# MAX96724_EVB_revB.net
KiCad netlist of a schematic drawn in Altium Designer
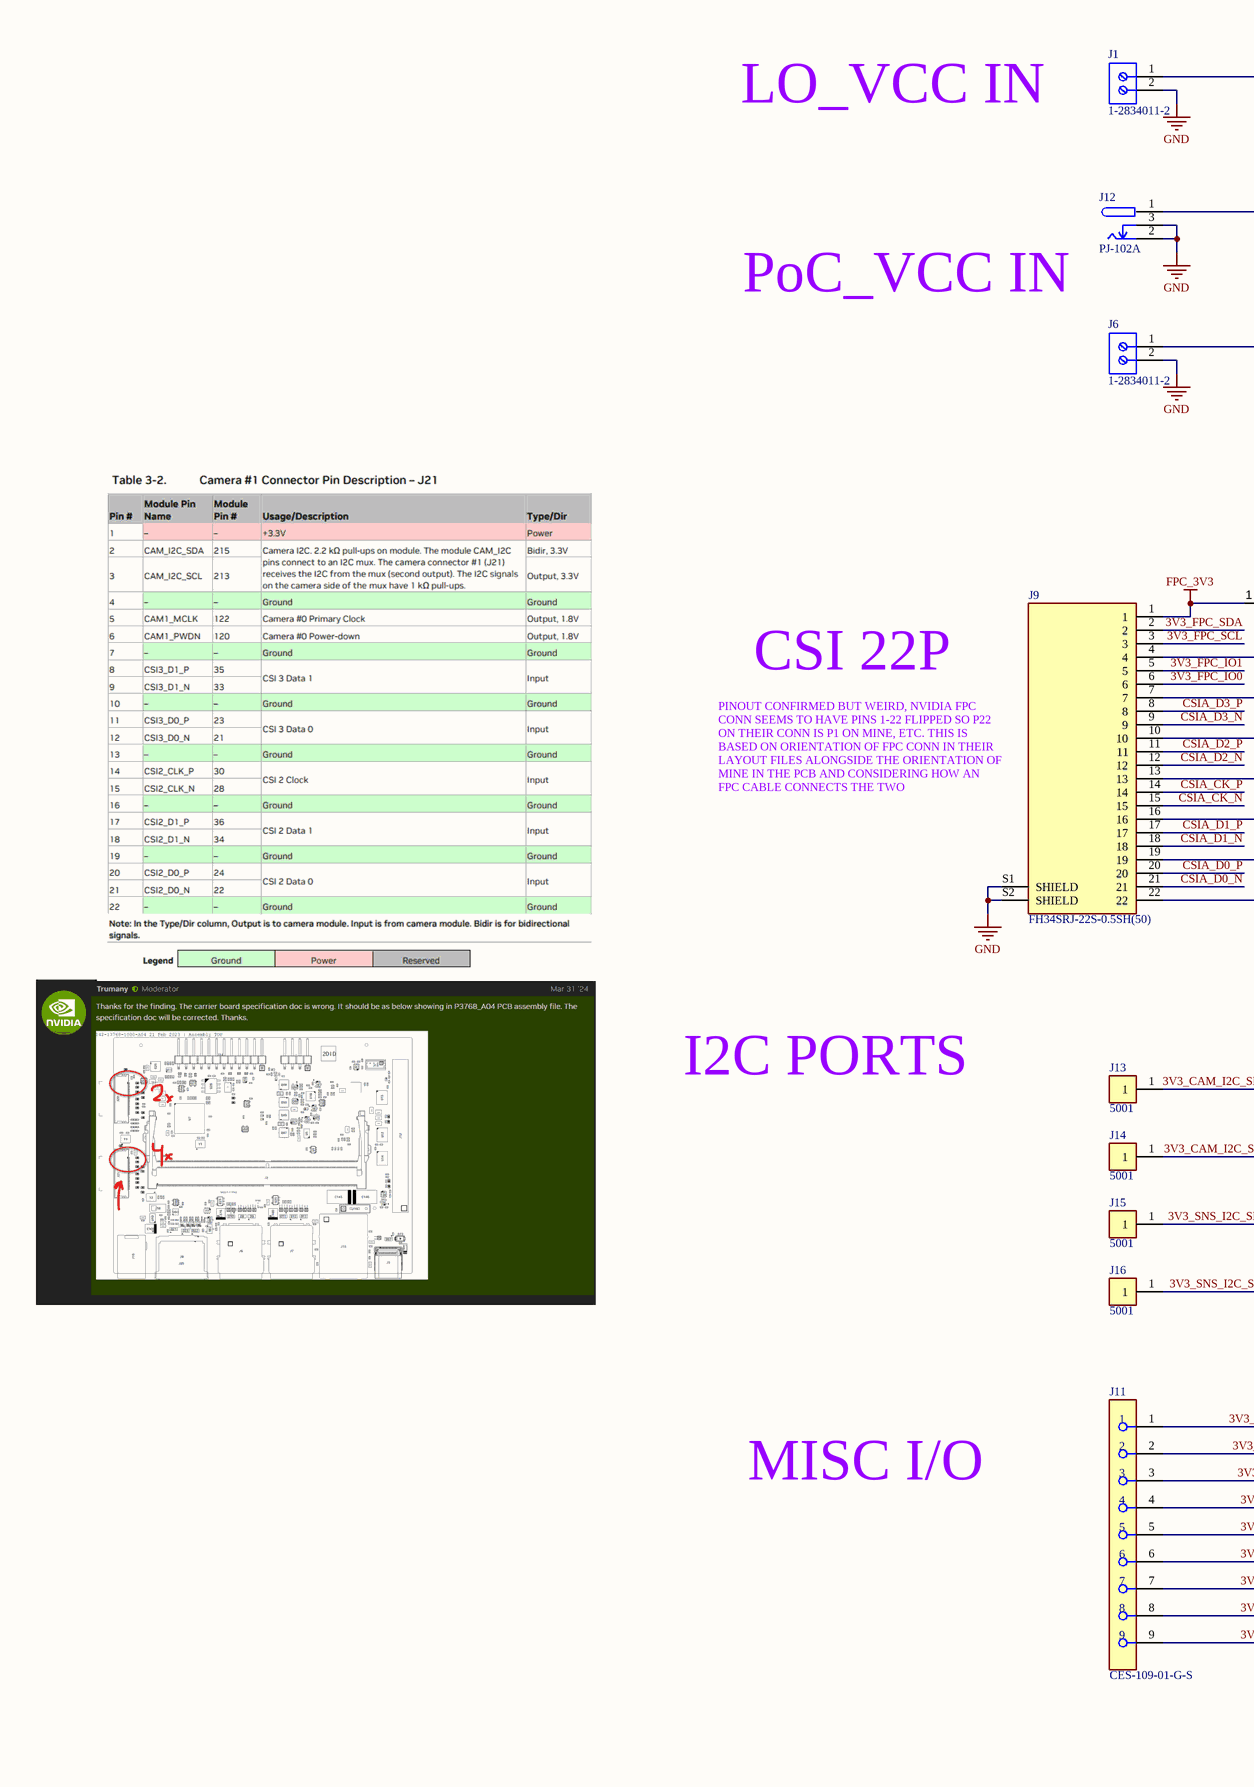
[diagram p0: MAX96724_EVB_revB.SchDoc, left]
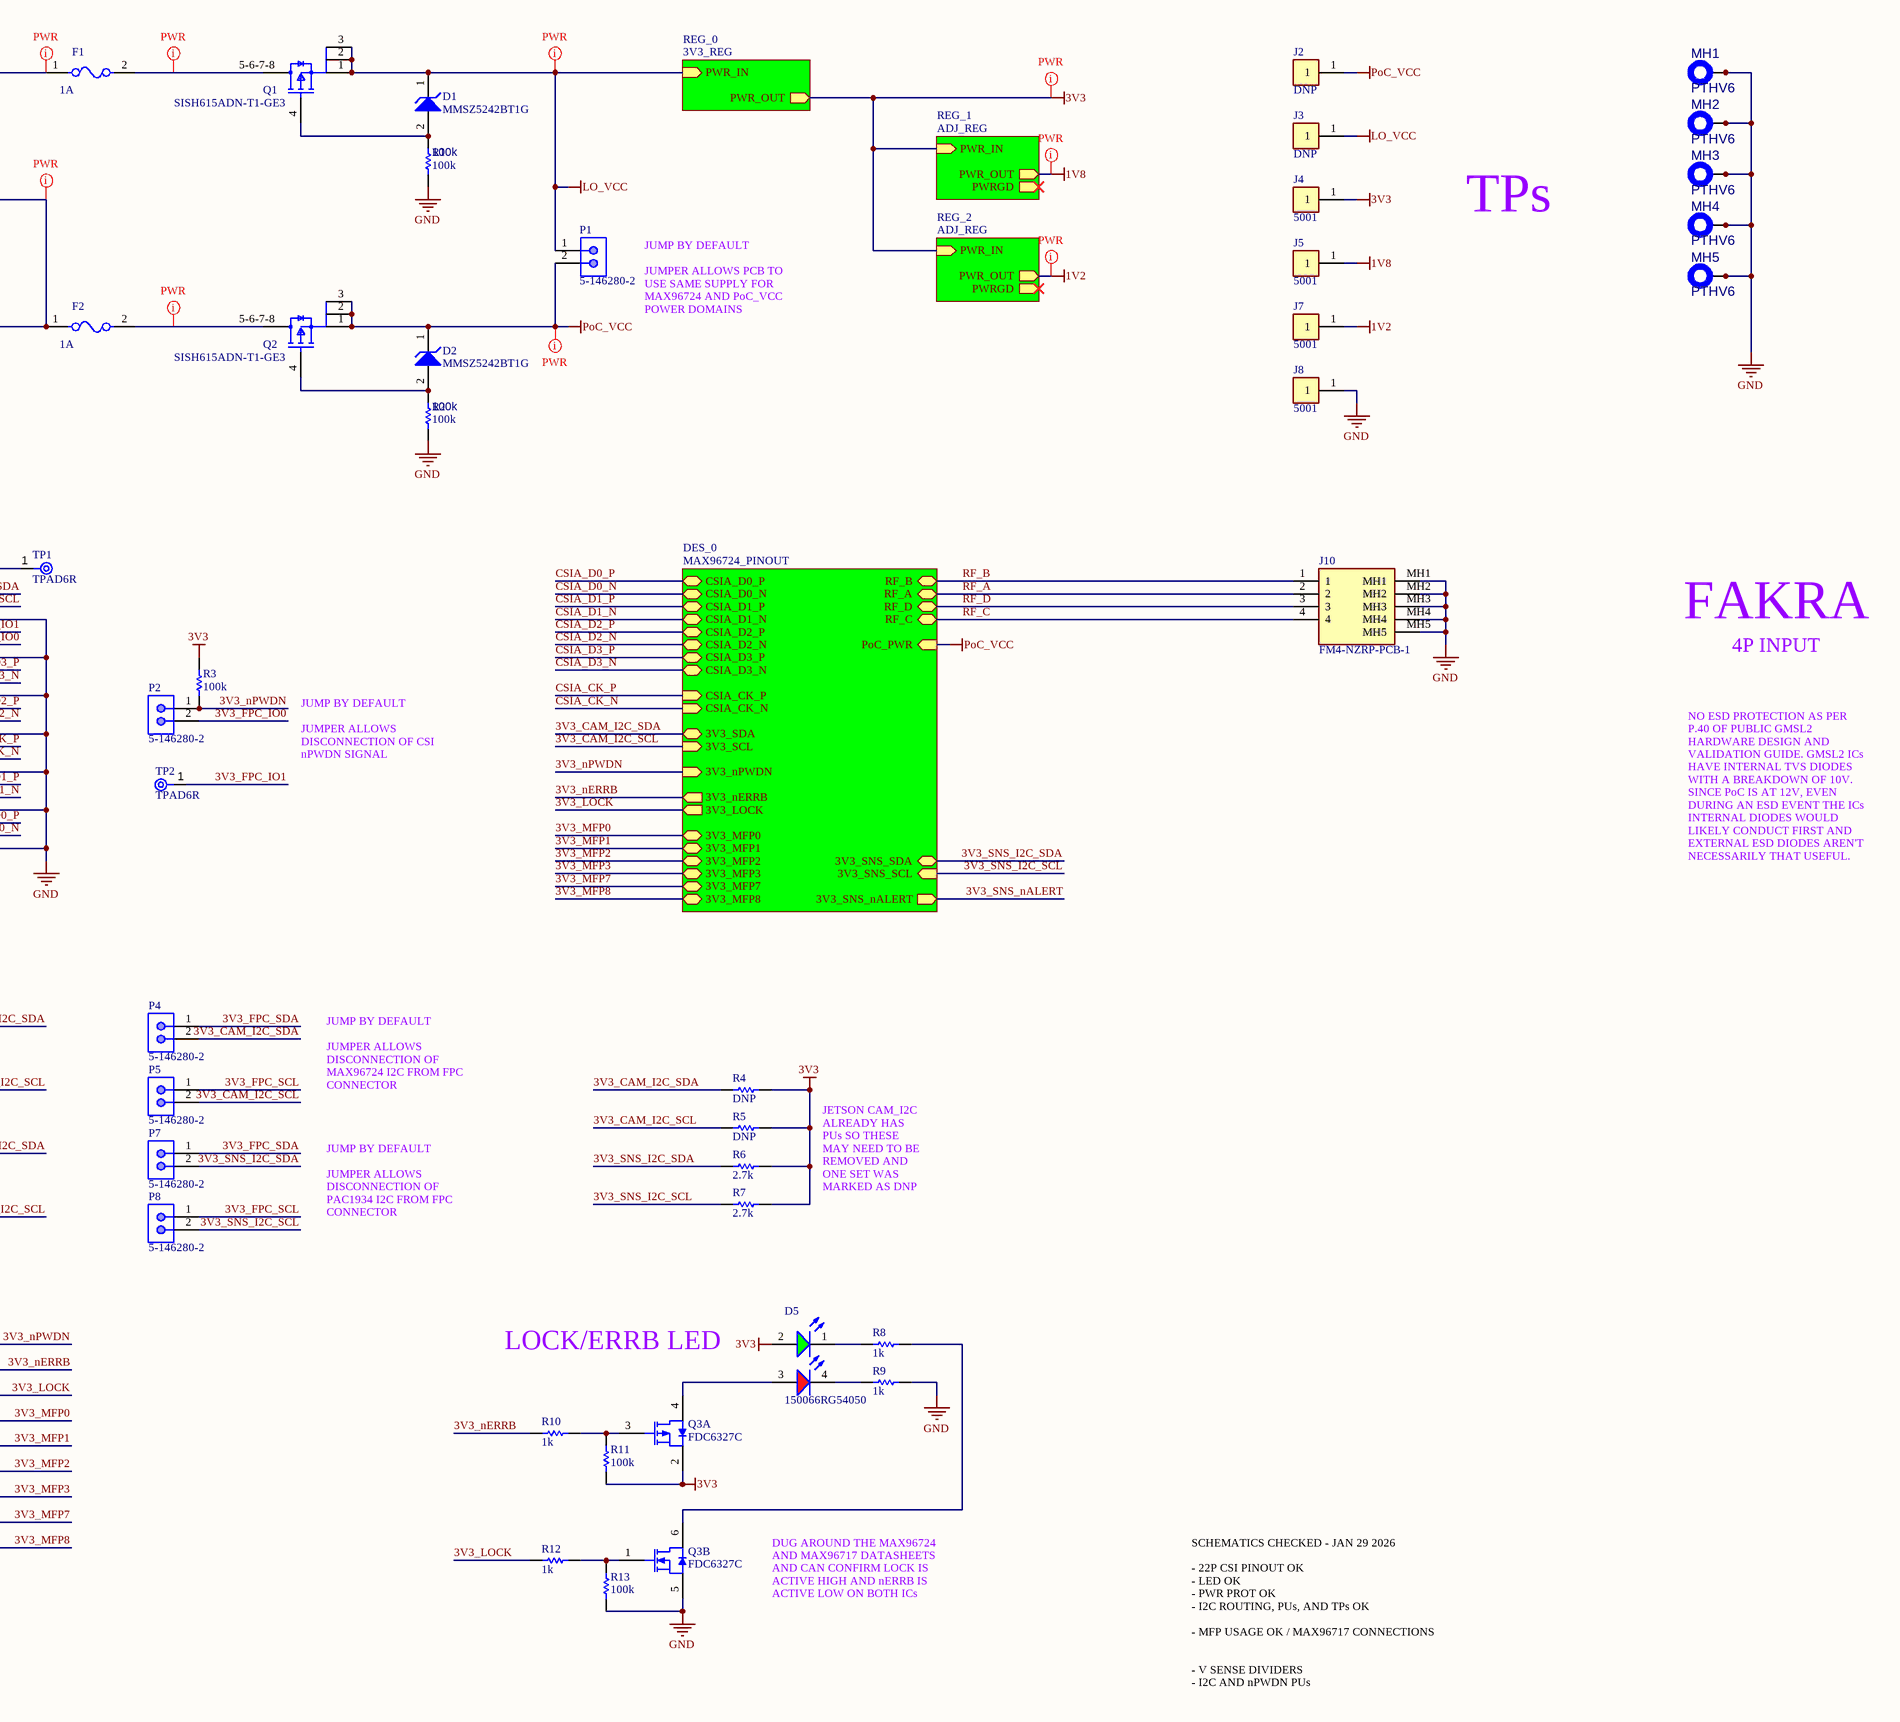
[diagram p1: MAX96724_EVB_revB.SchDoc, right]

(export (version "E")
  (design (tool "Eeschema 10.0.6"))
  (components
    (comp (ref "D1")
      (value "MMSZ5242BT1G")
      (footprint "ONSC-SOD-123-2-425-04_V")
      (description "Zener Voltage Regulator, 500 mW, 2-Pin SOD-123, Pb-Free, Tape and Reel")
      (fields (field (name "MANUFACTURER") "On Semiconductor"))
      (libsource (lib "Altium Content Vault") (part "ONSC-K1A2-2"))
    )
    (comp (ref "D2")
      (value "MMSZ5242BT1G")
      (footprint "ONSC-SOD-123-2-425-04_V")
      (description "Zener Voltage Regulator, 500 mW, 2-Pin SOD-123, Pb-Free, Tape and Reel")
      (fields (field (name "MANUFACTURER") "On Semiconductor"))
      (libsource (lib "Altium Content Vault") (part "ONSC-K1A2-2"))
    )
    (comp (ref "D5")
      (value "150066RG54050")
      (footprint "WL-SBCD_0606")
      (description "Led, Red/Grn, 180Mcd/230Mcd, 624Nm/525Nm Rohs Compliant: Yes")
      (fields (field (name "SOURCE") "rgled.SchLib"))
      (libsource (lib "Space Concordia") (part "CMP-004-00034-2"))
    )
    (comp (ref "F1")
      (value "1A")
      (footprint "FP-SF-1206FP-MFG")
      (description "FUSE BOARD MOUNT 2A 63VDC 1206")
      (libsource (lib "Altium Content Vault") (part "5bcf9b9f640e542cf0359d10258e979"))
    )
    (comp (ref "F2")
      (value "1A")
      (footprint "FP-SF-1206FP-MFG")
      (description "FUSE BOARD MOUNT 2A 63VDC 1206")
      (libsource (lib "Altium Content Vault") (part "5bcf9b9f640e542cf0359d10258e979"))
    )
    (comp (ref "J1")
      (value "1-2834011-2")
      (footprint "1-2834011-2-Footprint-1")
      (description "Barrier Strip Terminal Block")
      (libsource (lib "Space Concordia") (part "1-2834011-2"))
    )
    (comp (ref "J2")
      (value "DNP")
      (footprint "FP-5001-MFG")
      (description "PC TEST POINT MINIATURE BLACK")
      (libsource (lib "Altium Content Vault") (part "1e4615820a309e3ce90f9e6d957b7fa"))
    )
    (comp (ref "J3")
      (value "DNP")
      (footprint "FP-5001-MFG")
      (description "PC TEST POINT MINIATURE BLACK")
      (libsource (lib "Altium Content Vault") (part "1e4615820a309e3ce90f9e6d957b7fa"))
    )
    (comp (ref "J4")
      (value "5001")
      (footprint "FP-5001-MFG")
      (description "PC TEST POINT MINIATURE BLACK")
      (libsource (lib "Altium Content Vault") (part "1e4615820a309e3ce90f9e6d957b7fa"))
    )
    (comp (ref "J5")
      (value "5001")
      (footprint "FP-5001-MFG")
      (description "PC TEST POINT MINIATURE BLACK")
      (libsource (lib "Altium Content Vault") (part "1e4615820a309e3ce90f9e6d957b7fa"))
    )
    (comp (ref "J6")
      (value "1-2834011-2")
      (footprint "1-2834011-2-Footprint-1")
      (description "Barrier Strip Terminal Block")
      (libsource (lib "Space Concordia") (part "1-2834011-2"))
    )
    (comp (ref "J7")
      (value "5001")
      (footprint "FP-5001-MFG")
      (description "PC TEST POINT MINIATURE BLACK")
      (libsource (lib "Altium Content Vault") (part "1e4615820a309e3ce90f9e6d957b7fa"))
    )
    (comp (ref "J8")
      (value "5001")
      (footprint "FP-5001-MFG")
      (description "PC TEST POINT MINIATURE BLACK")
      (libsource (lib "Altium Content Vault") (part "1e4615820a309e3ce90f9e6d957b7fa"))
    )
    (comp (ref "J9")
      (value "FH34SRJ-22S-0.5SH(50)")
      (footprint "FH34SRJ-22S-0.5SH(50)-Footprint-1")
      (description "0.5Mm Pitch, 1.0Mm Height, Top And Bottom Contact, Back-Flip")
      (libsource (lib "Space Concordia") (part "FH34SRJ-22S-0.5SH(50)"))
    )
    (comp (ref "J10")
      (value "FM4-NZRP-PCB-1")
      (footprint "FM4-NZRP-PCB-1-Footprint-1")
      (description "Connector RF Mini-FAKRA Plug 9GHz 50Ohm Solder Right Angle Through Hole")
      (libsource (lib "Space Concordia") (part "CMP-002-00085-1"))
    )
    (comp (ref "J11")
      (value "CES-109-01-G-S")
      (footprint "FP-CES-109-01-G-S-MFG")
      (description "CES-109-01-G-S Conn Socket Strip SKT 9 POS 2.54mm Solder ST Top Entry Thru-Hole Tube")
      (libsource (lib "Altium Content Vault") (part "d3bf64047269a9dc9b641cdda8ee9d2"))
    )
    (comp (ref "J12")
      (value "PJ-102A")
      (footprint "FP-PJ-102A-MFG")
      (description "PJ-102A 2.0 x 6.5 mm, 2.5 A, Horizontal, Through Hole, Tapered Pins, Dc Power Jack Connector")
      (libsource (lib "Altium Content Vault") (part "c639f672d24b5d70918fa8d934b95d1"))
    )
    (comp (ref "J13")
      (value "5001")
      (footprint "FP-5001-MFG")
      (description "PC TEST POINT MINIATURE BLACK")
      (libsource (lib "Altium Content Vault") (part "1e4615820a309e3ce90f9e6d957b7fa"))
    )
    (comp (ref "J14")
      (value "5001")
      (footprint "FP-5001-MFG")
      (description "PC TEST POINT MINIATURE BLACK")
      (libsource (lib "Altium Content Vault") (part "1e4615820a309e3ce90f9e6d957b7fa"))
    )
    (comp (ref "J15")
      (value "5001")
      (footprint "FP-5001-MFG")
      (description "PC TEST POINT MINIATURE BLACK")
      (libsource (lib "Altium Content Vault") (part "1e4615820a309e3ce90f9e6d957b7fa"))
    )
    (comp (ref "J16")
      (value "5001")
      (footprint "FP-5001-MFG")
      (description "PC TEST POINT MINIATURE BLACK")
      (libsource (lib "Altium Content Vault") (part "1e4615820a309e3ce90f9e6d957b7fa"))
    )
    (comp (ref "MH1")
      (value "PTHV6")
      (footprint "PTHV6 M2")
      (libsource (lib "Space Concordia") (part "PTHV6"))
    )
    (comp (ref "MH2")
      (value "PTHV6")
      (footprint "PTHV6 M2")
      (libsource (lib "Space Concordia") (part "PTHV6"))
    )
    (comp (ref "MH3")
      (value "PTHV6")
      (footprint "PTHV6 M2")
      (libsource (lib "Space Concordia") (part "PTHV6"))
    )
    (comp (ref "MH4")
      (value "PTHV6")
      (footprint "PTHV6 M2")
      (libsource (lib "Space Concordia") (part "PTHV6"))
    )
    (comp (ref "MH5")
      (value "PTHV6")
      (footprint "PTHV6 M2")
      (libsource (lib "Space Concordia") (part "PTHV6"))
    )
    (comp (ref "P1")
      (value "5-146280-2")
      (footprint "TECO-5-146280-2_V")
      (fields (field (name "MANUFACTURER") "TE Connectivity"))
      (libsource (lib "") (part "CN-1P-M-R2_1"))
    )
    (comp (ref "P2")
      (value "5-146280-2")
      (footprint "TECO-5-146280-2_V")
      (fields (field (name "MANUFACTURER") "TE Connectivity"))
      (libsource (lib "Altium Content Vault") (part "CN-1P-M-R2"))
    )
    (comp (ref "P4")
      (value "5-146280-2")
      (footprint "TECO-5-146280-2_V")
      (fields (field (name "MANUFACTURER") "TE Connectivity"))
      (libsource (lib "Altium Content Vault") (part "CN-1P-M-R2"))
    )
    (comp (ref "P5")
      (value "5-146280-2")
      (footprint "TECO-5-146280-2_V")
      (fields (field (name "MANUFACTURER") "TE Connectivity"))
      (libsource (lib "Altium Content Vault") (part "CN-1P-M-R2"))
    )
    (comp (ref "P7")
      (value "5-146280-2")
      (footprint "TECO-5-146280-2_V")
      (fields (field (name "MANUFACTURER") "TE Connectivity"))
      (libsource (lib "Altium Content Vault") (part "CN-1P-M-R2"))
    )
    (comp (ref "P8")
      (value "5-146280-2")
      (footprint "TECO-5-146280-2_V")
      (fields (field (name "MANUFACTURER") "TE Connectivity"))
      (libsource (lib "Altium Content Vault") (part "CN-1P-M-R2"))
    )
    (comp (ref "Q1")
      (value "SISH615ADN-T1-GE3")
      (footprint "SISH615ADN-T1-GE3-Footprint-1")
      (description "Trans MOSFET P-CH 20V 22.1A 8-Pin PowerPAK 1212 EP T/R")
      (libsource (lib "Space Concordia") (part "CMP-013-00036-4"))
    )
    (comp (ref "Q2")
      (value "SISH615ADN-T1-GE3")
      (footprint "SISH615ADN-T1-GE3-Footprint-1")
      (description "Trans MOSFET P-CH 20V 22.1A 8-Pin PowerPAK 1212 EP T/R")
      (libsource (lib "Space Concordia") (part "CMP-013-00036-4"))
    )
    (comp (ref "Q3")
      (value "FDC6327C")
      (footprint "FAIR-SOT23-6_V")
      (fields (field (name "MANUFACTURER") "Fairchild"))
      (libsource (lib "Altium Content Vault") (part "PEMOS-SGD-NEMOS-GSD-6"))
    )
    (comp (ref "R1")
      (value "100k")
      (footprint "R0603B")
      (description "Resistor")
      (fields (field (name "ALTIUM_VALUE") "100k"))
      (libsource (lib "Space Concordia") (part "Resistor"))
    )
    (comp (ref "R2")
      (value "100k")
      (footprint "R0603B")
      (description "Resistor")
      (fields (field (name "ALTIUM_VALUE") "100k"))
      (libsource (lib "Space Concordia") (part "Resistor"))
    )
    (comp (ref "R3")
      (value "100k")
      (footprint "R0603B")
      (description "Resistor")
      (libsource (lib "Space Concordia") (part "Resistor"))
    )
    (comp (ref "R4")
      (value "DNP")
      (footprint "R0603B")
      (description "Resistor")
      (libsource (lib "Space Concordia") (part "Resistor"))
    )
    (comp (ref "R5")
      (value "DNP")
      (footprint "R0603B")
      (description "Resistor")
      (libsource (lib "Space Concordia") (part "Resistor"))
    )
    (comp (ref "R6")
      (value "2.7k")
      (footprint "R0603B")
      (description "Resistor")
      (libsource (lib "Space Concordia") (part "Resistor"))
    )
    (comp (ref "R7")
      (value "2.7k")
      (footprint "R0603B")
      (description "Resistor")
      (libsource (lib "Space Concordia") (part "Resistor"))
    )
    (comp (ref "R8")
      (value "1k")
      (footprint "R0603B")
      (description "Resistor")
      (libsource (lib "Space Concordia") (part "Resistor"))
    )
    (comp (ref "R9")
      (value "1k")
      (footprint "R0603B")
      (description "Resistor")
      (libsource (lib "Space Concordia") (part "Resistor"))
    )
    (comp (ref "R10")
      (value "1k")
      (footprint "R0603B")
      (description "Resistor")
      (libsource (lib "Space Concordia") (part "Resistor"))
    )
    (comp (ref "R11")
      (value "100k")
      (footprint "R0603B")
      (description "Resistor")
      (libsource (lib "Space Concordia") (part "Resistor"))
    )
    (comp (ref "R12")
      (value "1k")
      (footprint "R0603B")
      (description "Resistor")
      (libsource (lib "Space Concordia") (part "Resistor"))
    )
    (comp (ref "R13")
      (value "100k")
      (footprint "R0603B")
      (description "Resistor")
      (libsource (lib "Space Concordia") (part "Resistor"))
    )
    (comp (ref "TP1")
      (value "TPAD6R")
      (footprint "New footprint 1")
      (description "Test Point .6mm")
      (libsource (lib "Space Concordia") (part "TP"))
    )
    (comp (ref "TP2")
      (value "TPAD6R")
      (footprint "New footprint 1")
      (description "Test Point .6mm")
      (libsource (lib "Space Concordia") (part "TP"))
    )
  )
  (nets
    (net (code "1") (name "/3V3_CAM_I2C_SCL") (class "Default")
      (node (ref "J14") (pin "1") (pinfunction "1_1") (pintype "passive"))
      (node (ref "P5") (pin "2") (pinfunction "2_2") (pintype "passive"))
      (node (ref "R5") (pin "1") (pinfunction "1_1") (pintype "passive"))
    )
    (net (code "2") (name "/3V3_CAM_I2C_SDA") (class "Default")
      (node (ref "J13") (pin "1") (pinfunction "1_1") (pintype "passive"))
      (node (ref "P4") (pin "2") (pinfunction "2_2") (pintype "passive"))
      (node (ref "R4") (pin "1") (pinfunction "1_1") (pintype "passive"))
    )
    (net (code "3") (name "/3V3_FPC_IO0") (class "Default")
      (node (ref "J9") (pin "6") (pinfunction "6_6") (pintype "passive"))
      (node (ref "P2") (pin "2") (pinfunction "2_2") (pintype "passive"))
    )
    (net (code "4") (name "/3V3_FPC_IO1") (class "Default")
      (node (ref "J9") (pin "5") (pinfunction "5_5") (pintype "passive"))
      (node (ref "TP2") (pin "1") (pinfunction "TP_1") (pintype "passive"))
    )
    (net (code "5") (name "/3V3_FPC_SCL") (class "Default")
      (node (ref "J9") (pin "3") (pinfunction "3_3") (pintype "passive"))
      (node (ref "P5") (pin "1") (pinfunction "1_1") (pintype "passive"))
      (node (ref "P8") (pin "1") (pinfunction "1_1") (pintype "passive"))
    )
    (net (code "6") (name "/3V3_FPC_SDA") (class "Default")
      (node (ref "J9") (pin "2") (pinfunction "2_2") (pintype "passive"))
      (node (ref "P4") (pin "1") (pinfunction "1_1") (pintype "passive"))
      (node (ref "P7") (pin "1") (pinfunction "1_1") (pintype "passive"))
    )
    (net (code "7") (name "/3V3_LOCK") (class "Default")
      (node (ref "J11") (pin "3") (pinfunction "3_3") (pintype "passive"))
      (node (ref "R12") (pin "2") (pinfunction "2_2") (pintype "passive"))
    )
    (net (code "8") (name "/3V3_MFP0") (class "Default")
      (node (ref "J11") (pin "4") (pinfunction "4_4") (pintype "passive"))
    )
    (net (code "9") (name "/3V3_MFP1") (class "Default")
      (node (ref "J11") (pin "5") (pinfunction "5_5") (pintype "passive"))
    )
    (net (code "10") (name "/3V3_MFP2") (class "Default")
      (node (ref "J11") (pin "6") (pinfunction "6_6") (pintype "passive"))
    )
    (net (code "11") (name "/3V3_MFP3") (class "Default")
      (node (ref "J11") (pin "7") (pinfunction "7_7") (pintype "passive"))
    )
    (net (code "12") (name "/3V3_MFP7") (class "Default")
      (node (ref "J11") (pin "8") (pinfunction "8_8") (pintype "passive"))
    )
    (net (code "13") (name "/3V3_MFP8") (class "Default")
      (node (ref "J11") (pin "9") (pinfunction "9_9") (pintype "passive"))
    )
    (net (code "14") (name "/3V3_SNS_I2C_SCL") (class "Default")
      (node (ref "J16") (pin "1") (pinfunction "1_1") (pintype "passive"))
      (node (ref "P8") (pin "2") (pinfunction "2_2") (pintype "passive"))
      (node (ref "R7") (pin "1") (pinfunction "1_1") (pintype "passive"))
    )
    (net (code "15") (name "/3V3_SNS_I2C_SDA") (class "Default")
      (node (ref "J15") (pin "1") (pinfunction "1_1") (pintype "passive"))
      (node (ref "P7") (pin "2") (pinfunction "2_2") (pintype "passive"))
      (node (ref "R6") (pin "1") (pinfunction "1_1") (pintype "passive"))
    )
    (net (code "17") (name "/3V3_nERRB") (class "Default")
      (node (ref "J11") (pin "2") (pinfunction "2_2") (pintype "passive"))
      (node (ref "R10") (pin "1") (pinfunction "1_1") (pintype "passive"))
    )
    (net (code "18") (name "/3V3_nPWDN") (class "Default")
      (node (ref "J11") (pin "1") (pinfunction "1_1") (pintype "passive"))
      (node (ref "P2") (pin "1") (pinfunction "1_1") (pintype "passive"))
      (node (ref "R3") (pin "1") (pinfunction "1_1") (pintype "passive"))
    )
    (net (code "19") (name "/CSIA_CK_N") (class "Default")
      (node (ref "J9") (pin "15") (pinfunction "15_15") (pintype "passive"))
    )
    (net (code "20") (name "/CSIA_CK_P") (class "Default")
      (node (ref "J9") (pin "14") (pinfunction "14_14") (pintype "passive"))
    )
    (net (code "21") (name "/CSIA_D0_N") (class "Default")
      (node (ref "J9") (pin "21") (pinfunction "21_21") (pintype "passive"))
    )
    (net (code "22") (name "/CSIA_D0_P") (class "Default")
      (node (ref "J9") (pin "20") (pinfunction "20_20") (pintype "passive"))
    )
    (net (code "23") (name "/CSIA_D1_N") (class "Default")
      (node (ref "J9") (pin "18") (pinfunction "18_18") (pintype "passive"))
    )
    (net (code "24") (name "/CSIA_D1_P") (class "Default")
      (node (ref "J9") (pin "17") (pinfunction "17_17") (pintype "passive"))
    )
    (net (code "25") (name "/CSIA_D2_N") (class "Default")
      (node (ref "J9") (pin "12") (pinfunction "12_12") (pintype "passive"))
    )
    (net (code "26") (name "/CSIA_D2_P") (class "Default")
      (node (ref "J9") (pin "11") (pinfunction "11_11") (pintype "passive"))
    )
    (net (code "27") (name "/CSIA_D3_N") (class "Default")
      (node (ref "J9") (pin "9") (pinfunction "9_9") (pintype "passive"))
    )
    (net (code "28") (name "/CSIA_D3_P") (class "Default")
      (node (ref "J9") (pin "8") (pinfunction "8_8") (pintype "passive"))
    )
    (net (code "31") (name "/RF_A") (class "Default")
      (node (ref "J10") (pin "2") (pinfunction "2_2") (pintype "passive"))
    )
    (net (code "32") (name "/RF_B") (class "Default")
      (node (ref "J10") (pin "1") (pinfunction "1_1") (pintype "passive"))
    )
    (net (code "33") (name "/RF_C") (class "Default")
      (node (ref "J10") (pin "4") (pinfunction "4_4") (pintype "passive"))
    )
    (net (code "34") (name "/RF_D") (class "Default")
      (node (ref "J10") (pin "3") (pinfunction "3_3") (pintype "passive"))
    )
    (net (code "35") (name "1V2") (class "Default")
      (node (ref "J7") (pin "1") (pinfunction "1_1") (pintype "passive"))
    )
    (net (code "36") (name "1V8") (class "Default")
      (node (ref "J5") (pin "1") (pinfunction "1_1") (pintype "passive"))
    )
    (net (code "37") (name "3V3") (class "Default")
      (node (ref "D5") (pin "2") (pinfunction "A_2") (pintype "passive"))
      (node (ref "J4") (pin "1") (pinfunction "1_1") (pintype "passive"))
      (node (ref "Q3") (pin "2") (pinfunction "S_2") (pintype "passive"))
      (node (ref "R11") (pin "1") (pinfunction "1_1") (pintype "passive"))
      (node (ref "R3") (pin "2") (pinfunction "2_2") (pintype "passive"))
      (node (ref "R4") (pin "2") (pinfunction "2_2") (pintype "passive"))
      (node (ref "R5") (pin "2") (pinfunction "2_2") (pintype "passive"))
      (node (ref "R6") (pin "2") (pinfunction "2_2") (pintype "passive"))
      (node (ref "R7") (pin "2") (pinfunction "2_2") (pintype "passive"))
    )
    (net (code "38") (name "FPC_3V3") (class "Default")
      (node (ref "J9") (pin "1") (pinfunction "1_1") (pintype "passive"))
      (node (ref "TP1") (pin "1") (pinfunction "TP_1") (pintype "passive"))
    )
    (net (code "39") (name "GND") (class "Default")
      (node (ref "J1") (pin "2") (pinfunction "2_2") (pintype "passive"))
      (node (ref "J10") (pin "MH1") (pinfunction "MH1_MH1") (pintype "passive"))
      (node (ref "J10") (pin "MH2") (pinfunction "MH2_MH2") (pintype "passive"))
      (node (ref "J10") (pin "MH3") (pinfunction "MH3_MH3") (pintype "passive"))
      (node (ref "J10") (pin "MH4") (pinfunction "MH4_MH4") (pintype "passive"))
      (node (ref "J10") (pin "MH5") (pinfunction "MH5_MH5") (pintype "passive"))
      (node (ref "J12") (pin "2") (pinfunction "2_2") (pintype "passive"))
      (node (ref "J12") (pin "3") (pinfunction "3_3") (pintype "passive"))
      (node (ref "J6") (pin "2") (pinfunction "2_2") (pintype "passive"))
      (node (ref "J8") (pin "1") (pinfunction "1_1") (pintype "passive"))
      (node (ref "J9") (pin "10") (pinfunction "10_10") (pintype "passive"))
      (node (ref "J9") (pin "13") (pinfunction "13_13") (pintype "passive"))
      (node (ref "J9") (pin "16") (pinfunction "16_16") (pintype "passive"))
      (node (ref "J9") (pin "19") (pinfunction "19_19") (pintype "passive"))
      (node (ref "J9") (pin "22") (pinfunction "22_22") (pintype "passive"))
      (node (ref "J9") (pin "4") (pinfunction "4_4") (pintype "passive"))
      (node (ref "J9") (pin "7") (pinfunction "7_7") (pintype "passive"))
      (node (ref "J9") (pin "S1") (pinfunction "SHIELD_S1") (pintype "passive"))
      (node (ref "J9") (pin "S2") (pinfunction "SHIELD_S2") (pintype "passive"))
      (node (ref "MH1") (pin "1") (pinfunction "MH_1") (pintype "passive"))
      (node (ref "MH1") (pin "2") (pinfunction "V1_2") (pintype "passive"))
      (node (ref "MH1") (pin "3") (pinfunction "V2_3") (pintype "passive"))
      (node (ref "MH1") (pin "4") (pinfunction "V3_4") (pintype "passive"))
      (node (ref "MH1") (pin "5") (pinfunction "V4_5") (pintype "passive"))
      (node (ref "MH1") (pin "6") (pinfunction "V5_6") (pintype "passive"))
      (node (ref "MH1") (pin "7") (pinfunction "V6_7") (pintype "passive"))
      (node (ref "MH2") (pin "1") (pinfunction "MH_1") (pintype "passive"))
      (node (ref "MH2") (pin "2") (pinfunction "V1_2") (pintype "passive"))
      (node (ref "MH2") (pin "3") (pinfunction "V2_3") (pintype "passive"))
      (node (ref "MH2") (pin "4") (pinfunction "V3_4") (pintype "passive"))
      (node (ref "MH2") (pin "5") (pinfunction "V4_5") (pintype "passive"))
      (node (ref "MH2") (pin "6") (pinfunction "V5_6") (pintype "passive"))
      (node (ref "MH2") (pin "7") (pinfunction "V6_7") (pintype "passive"))
      (node (ref "MH3") (pin "1") (pinfunction "MH_1") (pintype "passive"))
      (node (ref "MH3") (pin "2") (pinfunction "V1_2") (pintype "passive"))
      (node (ref "MH3") (pin "3") (pinfunction "V2_3") (pintype "passive"))
      (node (ref "MH3") (pin "4") (pinfunction "V3_4") (pintype "passive"))
      (node (ref "MH3") (pin "5") (pinfunction "V4_5") (pintype "passive"))
      (node (ref "MH3") (pin "6") (pinfunction "V5_6") (pintype "passive"))
      (node (ref "MH3") (pin "7") (pinfunction "V6_7") (pintype "passive"))
      (node (ref "MH4") (pin "1") (pinfunction "MH_1") (pintype "passive"))
      (node (ref "MH4") (pin "2") (pinfunction "V1_2") (pintype "passive"))
      (node (ref "MH4") (pin "3") (pinfunction "V2_3") (pintype "passive"))
      (node (ref "MH4") (pin "4") (pinfunction "V3_4") (pintype "passive"))
      (node (ref "MH4") (pin "5") (pinfunction "V4_5") (pintype "passive"))
      (node (ref "MH4") (pin "6") (pinfunction "V5_6") (pintype "passive"))
      (node (ref "MH4") (pin "7") (pinfunction "V6_7") (pintype "passive"))
      (node (ref "MH5") (pin "1") (pinfunction "MH_1") (pintype "passive"))
      (node (ref "MH5") (pin "2") (pinfunction "V1_2") (pintype "passive"))
      (node (ref "MH5") (pin "3") (pinfunction "V2_3") (pintype "passive"))
      (node (ref "MH5") (pin "4") (pinfunction "V3_4") (pintype "passive"))
      (node (ref "MH5") (pin "5") (pinfunction "V4_5") (pintype "passive"))
      (node (ref "MH5") (pin "6") (pinfunction "V5_6") (pintype "passive"))
      (node (ref "MH5") (pin "7") (pinfunction "V6_7") (pintype "passive"))
      (node (ref "Q3") (pin "5") (pinfunction "S_5") (pintype "passive"))
      (node (ref "R1") (pin "1") (pinfunction "1_1") (pintype "passive"))
      (node (ref "R13") (pin "2") (pinfunction "2_2") (pintype "passive"))
      (node (ref "R2") (pin "1") (pinfunction "1_1") (pintype "passive"))
      (node (ref "R9") (pin "1") (pinfunction "1_1") (pintype "passive"))
    )
    (net (code "40") (name "LO_VCC") (class "Default")
      (node (ref "D1") (pin "1") (pinfunction "K_1") (pintype "passive"))
      (node (ref "J3") (pin "1") (pinfunction "1_1") (pintype "passive"))
      (node (ref "P1") (pin "1") (pinfunction "1_1") (pintype "passive"))
      (node (ref "Q1") (pin "1") (pinfunction "S_1") (pintype "passive"))
      (node (ref "Q1") (pin "2") (pinfunction "S_2") (pintype "passive"))
      (node (ref "Q1") (pin "3") (pinfunction "S_3") (pintype "passive"))
    )
    (net (code "41") (name "Net-(D1-A)") (class "Default")
      (node (ref "D1") (pin "2") (pinfunction "A_2") (pintype "passive"))
      (node (ref "Q1") (pin "4") (pinfunction "G_4") (pintype "passive"))
      (node (ref "R1") (pin "2") (pinfunction "2_2") (pintype "passive"))
    )
    (net (code "42") (name "Net-(D2-A)") (class "Default")
      (node (ref "D2") (pin "2") (pinfunction "A_2") (pintype "passive"))
      (node (ref "Q2") (pin "4") (pinfunction "G_4") (pintype "passive"))
      (node (ref "R2") (pin "2") (pinfunction "2_2") (pintype "passive"))
    )
    (net (code "43") (name "Net-(D5-K-Pad1)") (class "Default")
      (node (ref "D5") (pin "1") (pinfunction "K_1") (pintype "passive"))
      (node (ref "R8") (pin "2") (pinfunction "2_2") (pintype "passive"))
    )
    (net (code "44") (name "Net-(D5-K-Pad4)") (class "Default")
      (node (ref "D5") (pin "4") (pinfunction "K_4") (pintype "passive"))
      (node (ref "R9") (pin "2") (pinfunction "2_2") (pintype "passive"))
    )
    (net (code "45") (name "Net-(F1-Pad1)") (class "Default")
      (node (ref "F1") (pin "1") (pinfunction "1_1") (pintype "passive"))
      (node (ref "J1") (pin "1") (pinfunction "1_1") (pintype "passive"))
    )
    (net (code "46") (name "Net-(F2-Pad1)") (class "Default")
      (node (ref "F2") (pin "1") (pinfunction "1_1") (pintype "passive"))
      (node (ref "J12") (pin "1") (pinfunction "1_1") (pintype "passive"))
      (node (ref "J6") (pin "1") (pinfunction "1_1") (pintype "passive"))
    )
    (net (code "47") (name "Net-(Q1-D)") (class "Default")
      (node (ref "F1") (pin "2") (pinfunction "2_2") (pintype "passive"))
      (node (ref "Q1") (pin "5-6-7-8") (pinfunction "D_5-6-7-8") (pintype "passive"))
    )
    (net (code "48") (name "Net-(Q2-D)") (class "Default")
      (node (ref "F2") (pin "2") (pinfunction "2_2") (pintype "passive"))
      (node (ref "Q2") (pin "5-6-7-8") (pinfunction "D_5-6-7-8") (pintype "passive"))
    )
    (net (code "49") (name "Net-(Q3A-D)") (class "Default")
      (node (ref "D5") (pin "3") (pinfunction "A_3") (pintype "passive"))
      (node (ref "Q3") (pin "4") (pinfunction "D_4") (pintype "passive"))
    )
    (net (code "50") (name "Net-(Q3A-G)") (class "Default")
      (node (ref "Q3") (pin "3") (pinfunction "G_3") (pintype "passive"))
      (node (ref "R10") (pin "2") (pinfunction "2_2") (pintype "passive"))
      (node (ref "R11") (pin "2") (pinfunction "2_2") (pintype "passive"))
    )
    (net (code "51") (name "Net-(Q3B-D)") (class "Default")
      (node (ref "Q3") (pin "6") (pinfunction "D_6") (pintype "passive"))
      (node (ref "R8") (pin "1") (pinfunction "1_1") (pintype "passive"))
    )
    (net (code "52") (name "Net-(Q3B-G)") (class "Default")
      (node (ref "Q3") (pin "1") (pinfunction "G_1") (pintype "passive"))
      (node (ref "R12") (pin "1") (pinfunction "1_1") (pintype "passive"))
      (node (ref "R13") (pin "1") (pinfunction "1_1") (pintype "passive"))
    )
    (net (code "53") (name "PoC_VCC") (class "Default")
      (node (ref "D2") (pin "1") (pinfunction "K_1") (pintype "passive"))
      (node (ref "J2") (pin "1") (pinfunction "1_1") (pintype "passive"))
      (node (ref "P1") (pin "2") (pinfunction "2_2") (pintype "passive"))
      (node (ref "Q2") (pin "1") (pinfunction "S_1") (pintype "passive"))
      (node (ref "Q2") (pin "2") (pinfunction "S_2") (pintype "passive"))
      (node (ref "Q2") (pin "3") (pinfunction "S_3") (pintype "passive"))
    )
  )
)
